# LCD_Connector.net
KiCad netlist of a schematic drawn in Altium Designer
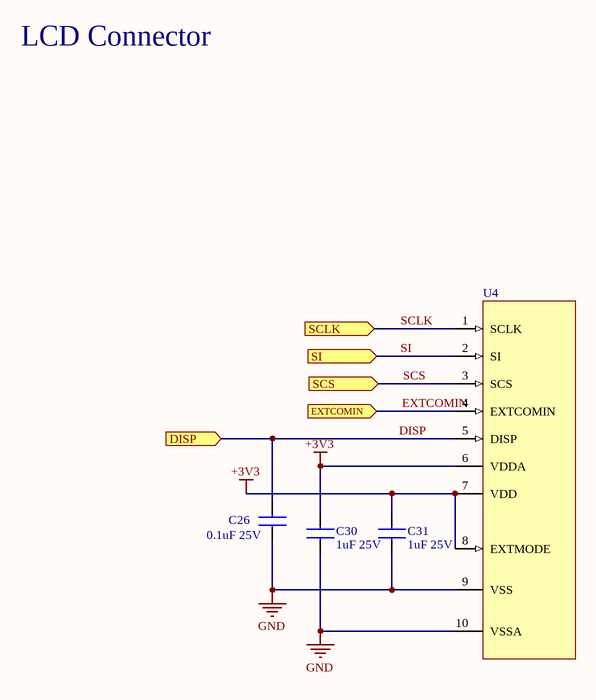
[diagram p0: LCD_Connector.SchDoc]

(export (version "E")
  (design (tool "Eeschema 10.0.6"))
  (components
    (comp (ref "C26")
      (value "0.1uF 25V")
      (footprint "Chip2Pin_1.6x0.8x0.9_CAP")
      (description "Cap Ceramic 0.1uF 25V X7R 10% Pad SMD 0603 Soft Termination 125C Automotive T/R")
      (fields
        (field (name "MANUFACTURER") "Murata")
        (field (name "MANUFACTURER PART NUMBER") "GCJ188R71E104KA12D")
      )
      (libsource (lib "LPEDT_Parts") (part "GCJ188R71E104KA12D"))
    )
    (comp (ref "C30")
      (value "1uF 25V")
      (footprint "Chip2Pin_1.6x0.8x0.9_CAP")
      (description "Cap Ceramic 1uF 25V X7R 10% Pad SMD 0603 125C Automotive T/R")
      (fields
        (field (name "MANUFACTURER") "Murata")
        (field (name "MANUFACTURER PART NUMBER") "GCM188R71E105KA64J")
      )
      (libsource (lib "LPEDT_Parts") (part "GCM188R71E105KA64J"))
    )
    (comp (ref "C31")
      (value "1uF 25V")
      (footprint "Chip2Pin_1.6x0.8x0.9_CAP")
      (description "Cap Ceramic 1uF 25V X7R 10% Pad SMD 0603 125C Automotive T/R")
      (fields
        (field (name "MANUFACTURER") "Murata")
        (field (name "MANUFACTURER PART NUMBER") "GCM188R71E105KA64J")
      )
      (libsource (lib "LPEDT_Parts") (part "GCM188R71E105KA64J"))
    )
    (comp (ref "U4")
      (value "10 Position FFC, FPC Connector Contacts, Top and Bottom 0.020\" (0.50mm) Surface Mount, Right Angle")
      (footprint "FFC_10POS_0.5MM_PITCH")
      (description "CONN FFC FPC 10POS 0.50MM R/A")
      (fields (field (name "MANUFACTURER") "Panasonic") (field (name "MANUFACTURER PART NUMBER") "AYF531035"))
      (libsource (lib "LPEDT_Parts") (part "AYF531035"))
    )
  )
  (nets
    (net (code "1") (name "+3V3") (class "Default")
      (node (ref "C30") (pin "1") (pinfunction "1_1") (pintype "passive"))
      (node (ref "C31") (pin "1") (pinfunction "1_1") (pintype "passive"))
      (node (ref "U4") (pin "6") (pinfunction "VDDA_6") (pintype "power_in"))
      (node (ref "U4") (pin "7") (pinfunction "VDD_7") (pintype "power_in"))
      (node (ref "U4") (pin "8") (pinfunction "EXTMODE_8") (pintype "input"))
    )
    (net (code "2") (name "/DISP") (class "Default")
      (node (ref "C26") (pin "1") (pinfunction "1_1") (pintype "passive"))
      (node (ref "U4") (pin "5") (pinfunction "DISP_5") (pintype "input"))
    )
    (net (code "3") (name "/EXTCOMIN") (class "Default")
      (node (ref "U4") (pin "4") (pinfunction "EXTCOMIN_4") (pintype "input"))
    )
    (net (code "4") (name "/SCLK") (class "Default")
      (node (ref "U4") (pin "1") (pinfunction "SCLK_1") (pintype "input"))
    )
    (net (code "5") (name "/SCS") (class "Default")
      (node (ref "U4") (pin "3") (pinfunction "SCS_3") (pintype "input"))
    )
    (net (code "6") (name "/SI") (class "Default")
      (node (ref "U4") (pin "2") (pinfunction "SI_2") (pintype "input"))
    )
    (net (code "7") (name "GND") (class "Default")
      (node (ref "C26") (pin "2") (pinfunction "2_2") (pintype "passive"))
      (node (ref "C30") (pin "2") (pinfunction "2_2") (pintype "passive"))
      (node (ref "C31") (pin "2") (pinfunction "2_2") (pintype "passive"))
      (node (ref "U4") (pin "10") (pinfunction "VSSA_10") (pintype "passive"))
      (node (ref "U4") (pin "9") (pinfunction "VSS_9") (pintype "passive"))
    )
  )
)
